# sparkledrive.net
KiCad netlist of a schematic drawn in EAGLE
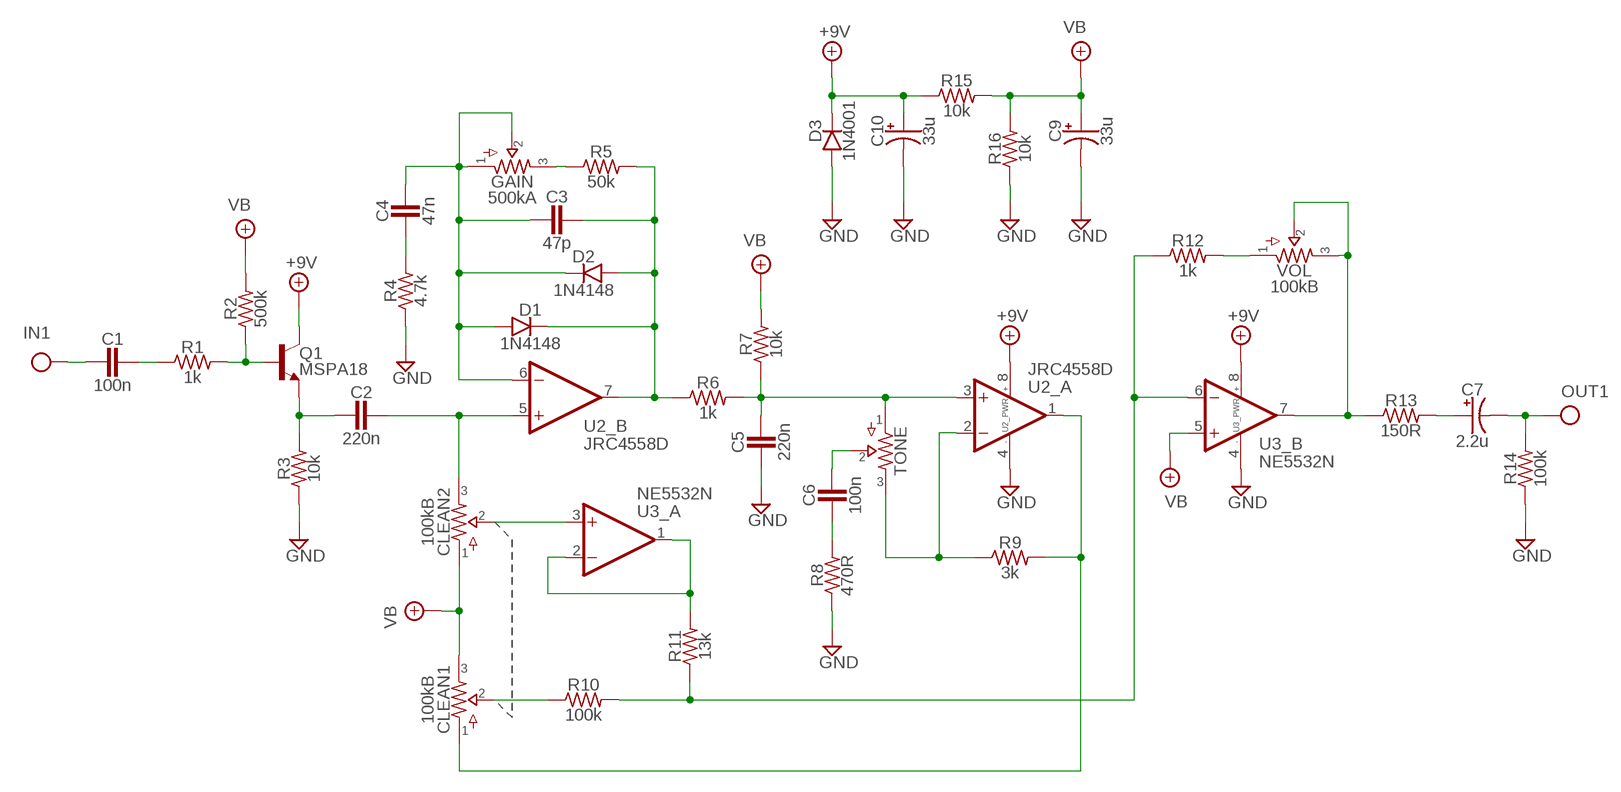
[diagram p0: schematic, sheet 1]

(export (version "E")
  (design (tool "Eeschema 10.0.6"))
  (components
    (comp (ref "C1")
      (value "100n")
      (footprint "eagle-import:BOX_SMALL")
      (libsource (lib "eagle-import") (part "CER/FILMBOX.1"))
    )
    (comp (ref "C2")
      (value "220n")
      (footprint "eagle-import:BOX_SMALL")
      (libsource (lib "eagle-import") (part "CER/FILMBOX.1"))
    )
    (comp (ref "C3")
      (value "47p")
      (footprint "eagle-import:BOX_SMALL")
      (libsource (lib "eagle-import") (part "CER/FILMBOX.1"))
    )
    (comp (ref "C4")
      (value "47n")
      (footprint "eagle-import:BOX_SMALL")
      (libsource (lib "eagle-import") (part "CER/FILMBOX.1"))
    )
    (comp (ref "C5")
      (value "220n")
      (footprint "eagle-import:BOX_SMALL")
      (libsource (lib "eagle-import") (part "CER/FILMBOX.1"))
    )
    (comp (ref "C6")
      (value "100n")
      (footprint "eagle-import:BOX_SMALL")
      (libsource (lib "eagle-import") (part "CER/FILMBOX.1"))
    )
    (comp (ref "C7")
      (value "2.2u")
      (footprint "eagle-import:050_020")
      (libsource (lib "eagle-import") (part "0500"))
    )
    (comp (ref "C9")
      (value "33u")
      (footprint "eagle-import:050_020")
      (libsource (lib "eagle-import") (part "0500"))
    )
    (comp (ref "C10")
      (value "33u")
      (footprint "eagle-import:050_020")
      (libsource (lib "eagle-import") (part "0500"))
    )
    (comp (ref "CLEAN1")
      (value "100kB")
      (footprint "eagle-import:16MM")
      (libsource (lib "eagle-import") (part "POTS16MM"))
    )
    (comp (ref "CLEAN2")
      (value "100kB")
      (footprint "eagle-import:16MM")
      (libsource (lib "eagle-import") (part "POTS16MM"))
    )
    (comp (ref "D1")
      (value "1N4148")
      (footprint "eagle-import:DO35-2")
      (libsource (lib "eagle-import") (part "DO35.2"))
    )
    (comp (ref "D2")
      (value "1N4148")
      (footprint "eagle-import:DO35-2")
      (libsource (lib "eagle-import") (part "DO35.2"))
    )
    (comp (ref "D3")
      (value "1N4001")
      (footprint "eagle-import:DO35-3")
      (libsource (lib "eagle-import") (part "DO35.3"))
    )
    (comp (ref "GAIN")
      (value "500kA")
      (footprint "eagle-import:16MM")
      (libsource (lib "eagle-import") (part "POTS16MM"))
    )
    (comp (ref "Q1")
      (value "MSPA18")
      (footprint "eagle-import:TO92-")
      (libsource (lib "eagle-import") (part "2N3904"))
    )
    (comp (ref "R1")
      (value "1k")
      (footprint "eagle-import:R0207_3")
      (libsource (lib "eagle-import") (part "R_.3B"))
    )
    (comp (ref "R2")
      (value "500k")
      (footprint "eagle-import:R0207_3")
      (libsource (lib "eagle-import") (part "R_.3B"))
    )
    (comp (ref "R3")
      (value "10k")
      (footprint "eagle-import:R0207_3")
      (libsource (lib "eagle-import") (part "R_.3B"))
    )
    (comp (ref "R4")
      (value "4.7k")
      (footprint "eagle-import:R0207_3")
      (libsource (lib "eagle-import") (part "R_.3B"))
    )
    (comp (ref "R5")
      (value "50k")
      (footprint "eagle-import:R0207_3")
      (libsource (lib "eagle-import") (part "R_.3B"))
    )
    (comp (ref "R6")
      (value "1k")
      (footprint "eagle-import:R0207_3")
      (libsource (lib "eagle-import") (part "R_.3B"))
    )
    (comp (ref "R7")
      (value "10k")
      (footprint "eagle-import:R0207_3")
      (libsource (lib "eagle-import") (part "R_.3B"))
    )
    (comp (ref "R8")
      (value "470R")
      (footprint "eagle-import:R0207_3")
      (libsource (lib "eagle-import") (part "R_.3B"))
    )
    (comp (ref "R9")
      (value "3k")
      (footprint "eagle-import:R0207_3")
      (libsource (lib "eagle-import") (part "R_.3B"))
    )
    (comp (ref "R10")
      (value "100k")
      (footprint "eagle-import:R0207_3")
      (libsource (lib "eagle-import") (part "R_.3B"))
    )
    (comp (ref "R11")
      (value "13k")
      (footprint "eagle-import:R0207_3")
      (libsource (lib "eagle-import") (part "R_.3B"))
    )
    (comp (ref "R12")
      (value "1k")
      (footprint "eagle-import:R0207_3")
      (libsource (lib "eagle-import") (part "R_.3B"))
    )
    (comp (ref "R13")
      (value "150R")
      (footprint "eagle-import:R0207_3")
      (libsource (lib "eagle-import") (part "R_.3B"))
    )
    (comp (ref "R14")
      (value "100k")
      (footprint "eagle-import:R0207_3")
      (libsource (lib "eagle-import") (part "R_.3B"))
    )
    (comp (ref "R15")
      (value "10k")
      (footprint "eagle-import:R0207_3")
      (libsource (lib "eagle-import") (part "R_.3B"))
    )
    (comp (ref "R16")
      (value "10k")
      (footprint "eagle-import:R0207_3")
      (libsource (lib "eagle-import") (part "R_.3B"))
    )
    (comp (ref "TONE")
      (value "POTS16MM")
      (footprint "eagle-import:16MM")
      (libsource (lib "eagle-import") (part "POTS16MM"))
    )
    (comp (ref "U2")
      (value "JRC4558D")
      (footprint "eagle-import:DIL0")
      (libsource (lib "eagle-import") (part "DUALTH"))
    )
    (comp (ref "U3")
      (value "NE5532N")
      (footprint "eagle-import:DIL0")
      (libsource (lib "eagle-import") (part "DUALTH"))
    )
    (comp (ref "VOL")
      (value "100kB")
      (footprint "eagle-import:16MM")
      (libsource (lib "eagle-import") (part "POTS16MM"))
    )
  )
  (nets
    (net (code "1") (name "+9V") (class "Default")
      (node (ref "C10") (pin "+") (pinfunction "+_+") (pintype "passive"))
      (node (ref "D3") (pin "C") (pinfunction "C_C") (pintype "passive"))
      (node (ref "Q1") (pin "1") (pinfunction "C_1") (pintype "passive"))
      (node (ref "R15") (pin "1") (pinfunction "1_1") (pintype "passive"))
      (node (ref "U2") (pin "8") (pinfunction "V+_8") (pintype "power_in"))
      (node (ref "U3") (pin "8") (pinfunction "V+_8") (pintype "power_in"))
    )
    (net (code "2") (name "GND") (class "Default")
      (node (ref "C10") (pin "-") (pinfunction "-_-") (pintype "passive"))
      (node (ref "C5") (pin "2") (pinfunction "2_2") (pintype "passive"))
      (node (ref "C9") (pin "-") (pinfunction "-_-") (pintype "passive"))
      (node (ref "D3") (pin "A") (pinfunction "A_A") (pintype "passive"))
      (node (ref "R14") (pin "1") (pinfunction "1_1") (pintype "passive"))
      (node (ref "R16") (pin "1") (pinfunction "1_1") (pintype "passive"))
      (node (ref "R3") (pin "1") (pinfunction "1_1") (pintype "passive"))
      (node (ref "R4") (pin "1") (pinfunction "1_1") (pintype "passive"))
      (node (ref "R8") (pin "1") (pinfunction "1_1") (pintype "passive"))
      (node (ref "U2") (pin "4") (pinfunction "V-_4") (pintype "power_in"))
      (node (ref "U3") (pin "4") (pinfunction "V-_4") (pintype "power_in"))
    )
    (net (code "3") (name "IN") (class "Default")
      (node (ref "C1") (pin "2") (pinfunction "2_2") (pintype "passive"))
    )
    (net (code "4") (name "Net-(C1-Pad1)") (class "Default")
      (node (ref "C1") (pin "1") (pinfunction "1_1") (pintype "passive"))
      (node (ref "R1") (pin "1") (pinfunction "1_1") (pintype "passive"))
    )
    (net (code "5") (name "Net-(C4-Pad2)") (class "Default")
      (node (ref "C4") (pin "2") (pinfunction "2_2") (pintype "passive"))
      (node (ref "R4") (pin "2") (pinfunction "2_2") (pintype "passive"))
    )
    (net (code "6") (name "Net-(C6-Pad1)") (class "Default")
      (node (ref "C6") (pin "1") (pinfunction "1_1") (pintype "passive"))
      (node (ref "TONE") (pin "2") (pinfunction "2_2") (pintype "passive"))
    )
    (net (code "7") (name "Net-(C6-Pad2)") (class "Default")
      (node (ref "C6") (pin "2") (pinfunction "2_2") (pintype "passive"))
      (node (ref "R8") (pin "2") (pinfunction "2_2") (pintype "passive"))
    )
    (net (code "8") (name "Net-(C7-Pad+)") (class "Default")
      (node (ref "C7") (pin "+") (pinfunction "+_+") (pintype "passive"))
      (node (ref "R13") (pin "2") (pinfunction "2_2") (pintype "passive"))
    )
    (net (code "9") (name "Net-(CLEAN1-Pad2)") (class "Default")
      (node (ref "CLEAN1") (pin "2") (pinfunction "2_2") (pintype "passive"))
      (node (ref "R10") (pin "1") (pinfunction "1_1") (pintype "passive"))
    )
    (net (code "10") (name "Net-(GAIN-Pad3)") (class "Default")
      (node (ref "GAIN") (pin "3") (pinfunction "3_3") (pintype "passive"))
      (node (ref "R5") (pin "1") (pinfunction "1_1") (pintype "passive"))
    )
    (net (code "11") (name "Net-(Q1-B)") (class "Default")
      (node (ref "Q1") (pin "2") (pinfunction "B_2") (pintype "passive"))
      (node (ref "R1") (pin "2") (pinfunction "2_2") (pintype "passive"))
      (node (ref "R2") (pin "1") (pinfunction "1_1") (pintype "passive"))
    )
    (net (code "12") (name "Net-(Q1-E)") (class "Default")
      (node (ref "C2") (pin "2") (pinfunction "2_2") (pintype "passive"))
      (node (ref "Q1") (pin "3") (pinfunction "E_3") (pintype "passive"))
      (node (ref "R3") (pin "2") (pinfunction "2_2") (pintype "passive"))
    )
    (net (code "13") (name "Net-(R12-Pad2)") (class "Default")
      (node (ref "R12") (pin "2") (pinfunction "2_2") (pintype "passive"))
      (node (ref "VOL") (pin "1") (pinfunction "1_1") (pintype "passive"))
    )
    (net (code "14") (name "Net-(U2A-+IN)") (class "Default")
      (node (ref "C5") (pin "1") (pinfunction "1_1") (pintype "passive"))
      (node (ref "R6") (pin "2") (pinfunction "2_2") (pintype "passive"))
      (node (ref "R7") (pin "1") (pinfunction "1_1") (pintype "passive"))
      (node (ref "TONE") (pin "1") (pinfunction "1_1") (pintype "passive"))
      (node (ref "U2") (pin "3") (pinfunction "+IN_3") (pintype "input"))
    )
    (net (code "15") (name "Net-(U2A--IN)") (class "Default")
      (node (ref "R9") (pin "1") (pinfunction "1_1") (pintype "passive"))
      (node (ref "TONE") (pin "3") (pinfunction "3_3") (pintype "passive"))
      (node (ref "U2") (pin "2") (pinfunction "-IN_2") (pintype "input"))
    )
    (net (code "16") (name "Net-(U2A-OUT)") (class "Default")
      (node (ref "CLEAN1") (pin "1") (pinfunction "1_1") (pintype "passive"))
      (node (ref "R9") (pin "2") (pinfunction "2_2") (pintype "passive"))
      (node (ref "U2") (pin "1") (pinfunction "OUT_1") (pintype "output"))
    )
    (net (code "17") (name "Net-(U2B-+IN)") (class "Default")
      (node (ref "C2") (pin "1") (pinfunction "1_1") (pintype "passive"))
      (node (ref "CLEAN2") (pin "3") (pinfunction "3_3") (pintype "passive"))
      (node (ref "U2") (pin "5") (pinfunction "+IN_5") (pintype "input"))
    )
    (net (code "18") (name "Net-(U2B--IN)") (class "Default")
      (node (ref "C3") (pin "2") (pinfunction "2_2") (pintype "passive"))
      (node (ref "C4") (pin "1") (pinfunction "1_1") (pintype "passive"))
      (node (ref "D1") (pin "A") (pinfunction "A_A") (pintype "passive"))
      (node (ref "D2") (pin "C") (pinfunction "C_C") (pintype "passive"))
      (node (ref "GAIN") (pin "1") (pinfunction "1_1") (pintype "passive"))
      (node (ref "GAIN") (pin "2") (pinfunction "2_2") (pintype "passive"))
      (node (ref "U2") (pin "6") (pinfunction "-IN_6") (pintype "input"))
    )
    (net (code "19") (name "Net-(U2B-OUT)") (class "Default")
      (node (ref "C3") (pin "1") (pinfunction "1_1") (pintype "passive"))
      (node (ref "D1") (pin "C") (pinfunction "C_C") (pintype "passive"))
      (node (ref "D2") (pin "A") (pinfunction "A_A") (pintype "passive"))
      (node (ref "R5") (pin "2") (pinfunction "2_2") (pintype "passive"))
      (node (ref "R6") (pin "1") (pinfunction "1_1") (pintype "passive"))
      (node (ref "U2") (pin "7") (pinfunction "OUT_7") (pintype "output"))
    )
    (net (code "20") (name "Net-(U3A-+IN)") (class "Default")
      (node (ref "CLEAN2") (pin "2") (pinfunction "2_2") (pintype "passive"))
      (node (ref "U3") (pin "3") (pinfunction "+IN_3") (pintype "input"))
    )
    (net (code "21") (name "Net-(U3A--IN)") (class "Default")
      (node (ref "R11") (pin "2") (pinfunction "2_2") (pintype "passive"))
      (node (ref "U3") (pin "1") (pinfunction "OUT_1") (pintype "output"))
      (node (ref "U3") (pin "2") (pinfunction "-IN_2") (pintype "input"))
    )
    (net (code "22") (name "Net-(U3B--IN)") (class "Default")
      (node (ref "R10") (pin "2") (pinfunction "2_2") (pintype "passive"))
      (node (ref "R11") (pin "1") (pinfunction "1_1") (pintype "passive"))
      (node (ref "R12") (pin "1") (pinfunction "1_1") (pintype "passive"))
      (node (ref "U3") (pin "6") (pinfunction "-IN_6") (pintype "input"))
    )
    (net (code "23") (name "Net-(U3B-OUT)") (class "Default")
      (node (ref "R13") (pin "1") (pinfunction "1_1") (pintype "passive"))
      (node (ref "U3") (pin "7") (pinfunction "OUT_7") (pintype "output"))
      (node (ref "VOL") (pin "2") (pinfunction "2_2") (pintype "passive"))
      (node (ref "VOL") (pin "3") (pinfunction "3_3") (pintype "passive"))
    )
    (net (code "24") (name "OUT") (class "Default")
      (node (ref "C7") (pin "-") (pinfunction "-_-") (pintype "passive"))
      (node (ref "R14") (pin "2") (pinfunction "2_2") (pintype "passive"))
    )
    (net (code "25") (name "VB") (class "Default")
      (node (ref "C9") (pin "+") (pinfunction "+_+") (pintype "passive"))
      (node (ref "CLEAN1") (pin "3") (pinfunction "3_3") (pintype "passive"))
      (node (ref "CLEAN2") (pin "1") (pinfunction "1_1") (pintype "passive"))
      (node (ref "R15") (pin "2") (pinfunction "2_2") (pintype "passive"))
      (node (ref "R16") (pin "2") (pinfunction "2_2") (pintype "passive"))
      (node (ref "R2") (pin "2") (pinfunction "2_2") (pintype "passive"))
      (node (ref "R7") (pin "2") (pinfunction "2_2") (pintype "passive"))
      (node (ref "U3") (pin "5") (pinfunction "+IN_5") (pintype "input"))
    )
  )
)
